# Top.net
KiCad netlist of a schematic drawn in Altium Designer
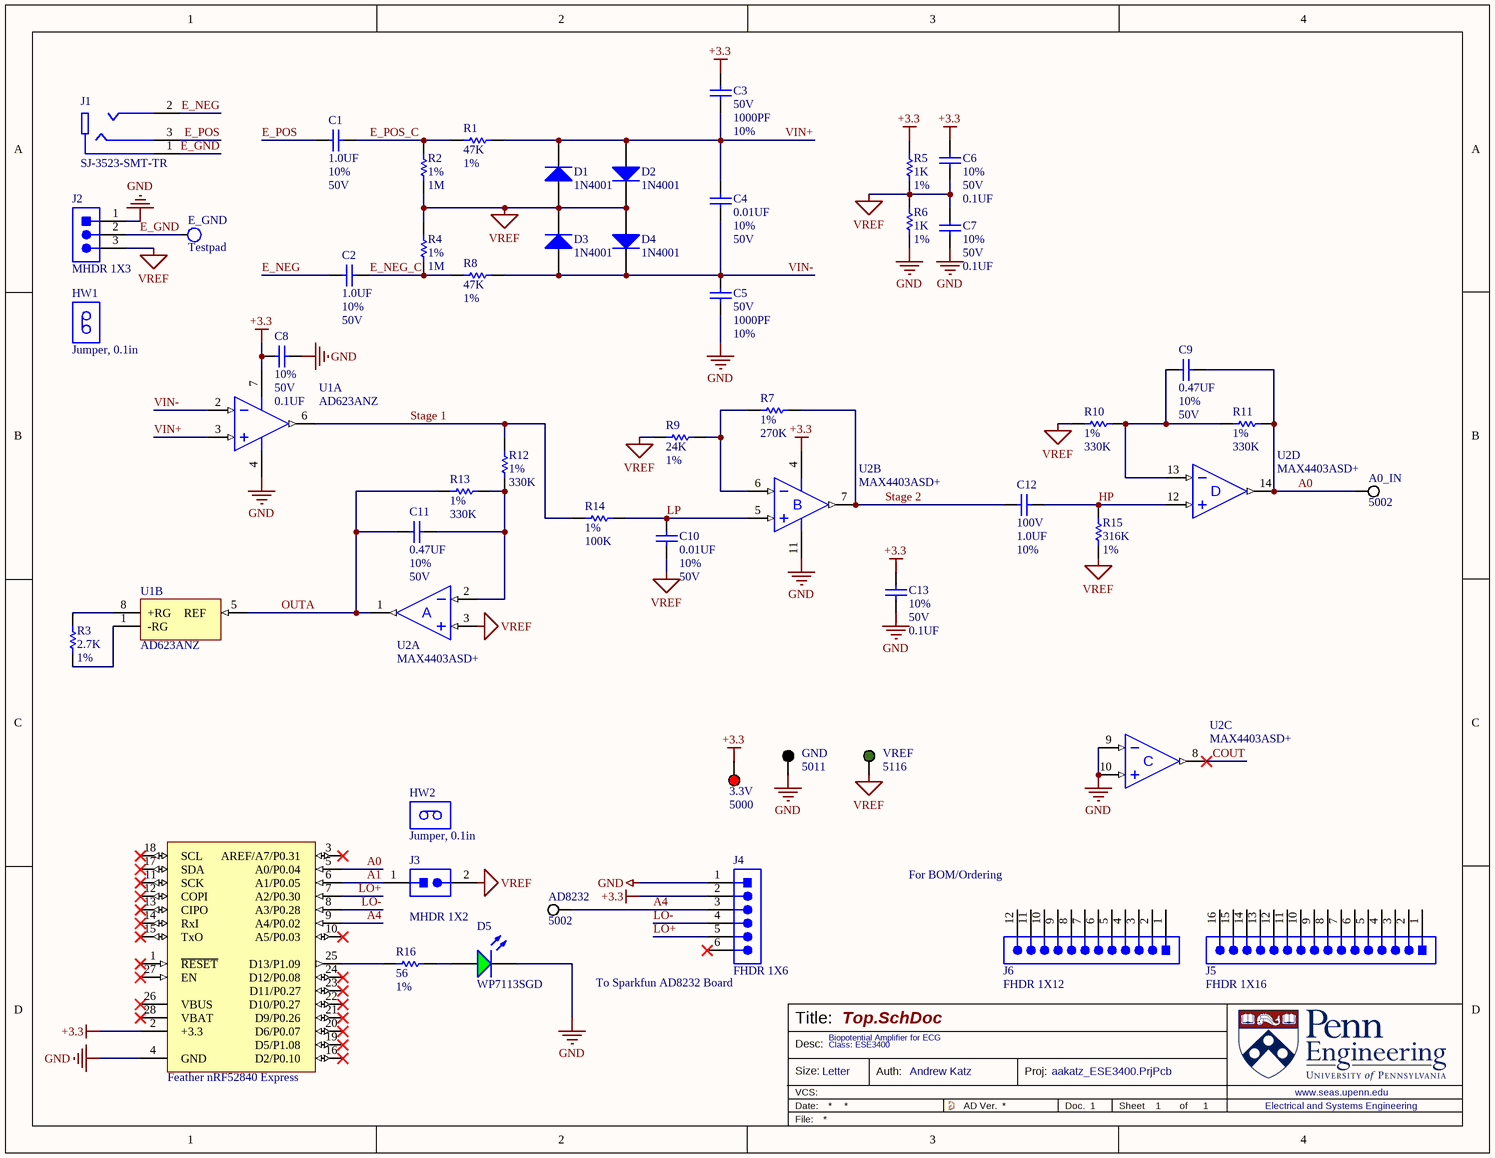
[diagram p0: Top.SchDoc]

(export (version "E")
  (design (tool "Eeschema 10.0.6"))
  (components
    (comp (ref "3.3V")
      (value "5000")
      (footprint "KSTN-5000")
      (description "Test Point, Red, 1-Pin THD, RoHS, Bulk")
      (fields (field (name "MANUFACTURER") "KeystoneElectronics"))
      (libsource (lib "University of Pennsylvania (ESE Labs)") (part "5000"))
    )
    (comp (ref "A0_IN")
      (value "5002")
      (footprint "KSTN-5002")
      (description "Test Point, White, 1-Pin THD, RoHS, Bulk")
      (fields (field (name "MANUFACTURER") "KeystoneElectronics"))
      (libsource (lib "University of Pennsylvania (ESE Labs)") (part "5002"))
    )
    (comp (ref "A1")
      (value "Feather nRF52840 Express")
      (footprint "4062-Stacking Headers")
      (description "Adafruit Feather nRF52840 Express (4062)")
      (libsource (lib "University of Pennsylvania (ESE Labs)") (part "4062-Symbol-1"))
    )
    (comp (ref "AD8232")
      (value "5002")
      (footprint "KSTN-5002")
      (description "Test Point, White, 1-Pin THD, RoHS, Bulk")
      (fields (field (name "MANUFACTURER") "KeystoneElectronics"))
      (libsource (lib "University of Pennsylvania (ESE Labs)") (part "5002"))
    )
    (comp (ref "C1")
      (value "1.0UF")
      (footprint "1206_CAP")
      (description "Capacitor Surface Mount 1206 Footprint 1.0UF 50V 10% Tolerance Ceramic X7R")
      (fields
        (field (name "TOLERANCE") "10%")
        (field (name "VOLTAGE") "50V")
        (field (name "MANUFACTURER") "Various")
        (field (name "Comment") "CAP 1206 1.0UF 50V 10% X7R")
      )
      (libsource (lib "University of Pennsylvania (ESE Labs)") (part "cap"))
    )
    (comp (ref "C2")
      (value "1.0UF")
      (footprint "1206_CAP")
      (description "Capacitor Surface Mount 1206 Footprint 1.0UF 50V 10% Tolerance Ceramic X7R")
      (fields
        (field (name "TOLERANCE") "10%")
        (field (name "VOLTAGE") "50V")
        (field (name "MANUFACTURER") "Various")
        (field (name "Comment") "CAP 1206 1.0UF 50V 10% X7R")
      )
      (libsource (lib "University of Pennsylvania (ESE Labs)") (part "cap"))
    )
    (comp (ref "C3")
      (value "1000PF")
      (footprint "1206_CAP")
      (description "Capacitor Surface Mount 1206 Footprint 1000PF 50V 10% Tolerance Ceramic X7R")
      (fields
        (field (name "VOLTAGE") "50V")
        (field (name "TOLERANCE") "10%")
        (field (name "MANUFACTURER") "Various")
        (field (name "Comment") "CAP 1206 1000PF 50V 10% X7R")
      )
      (libsource (lib "University of Pennsylvania (ESE Labs)") (part "cap"))
    )
    (comp (ref "C4")
      (value "0.01UF")
      (footprint "1206_CAP")
      (description "Capacitor Surface Mount 1206 Footprint 0.01UF 50V 10% Tolerance Ceramic X7R")
      (fields
        (field (name "MANUFACTURER") "Various")
        (field (name "TOLERANCE") "10%")
        (field (name "VOLTAGE") "50V")
        (field (name "Comment") "CAP 1206 0.01UF 50V 10% X7R")
      )
      (libsource (lib "University of Pennsylvania (ESE Labs)") (part "cap"))
    )
    (comp (ref "C5")
      (value "1000PF")
      (footprint "1206_CAP")
      (description "Capacitor Surface Mount 1206 Footprint 1000PF 50V 10% Tolerance Ceramic X7R")
      (fields
        (field (name "VOLTAGE") "50V")
        (field (name "TOLERANCE") "10%")
        (field (name "MANUFACTURER") "Various")
        (field (name "Comment") "CAP 1206 1000PF 50V 10% X7R")
      )
      (libsource (lib "University of Pennsylvania (ESE Labs)") (part "cap"))
    )
    (comp (ref "C6")
      (value "0.1UF")
      (footprint "1206_cap_35H")
      (description "Capacitor Surface Mount 1206 Footprint 0.1UF 50V 10% Tolerance Ceramic X7R")
      (fields
        (field (name "TOLERANCE") "10%")
        (field (name "MANUFACTURER") "KEMET")
        (field (name "VOLTAGE") "50V")
        (field (name "Comment") "CAP 1206 0.1UF 50V 10% X7R")
      )
      (libsource (lib "University of Pennsylvania (ESE Labs)") (part "cap"))
    )
    (comp (ref "C7")
      (value "0.1UF")
      (footprint "1206_cap_35H")
      (description "Capacitor Surface Mount 1206 Footprint 0.1UF 50V 10% Tolerance Ceramic X7R")
      (fields
        (field (name "TOLERANCE") "10%")
        (field (name "MANUFACTURER") "KEMET")
        (field (name "VOLTAGE") "50V")
        (field (name "Comment") "CAP 1206 0.1UF 50V 10% X7R")
      )
      (libsource (lib "University of Pennsylvania (ESE Labs)") (part "cap"))
    )
    (comp (ref "C8")
      (value "0.1UF")
      (footprint "1206_cap_35H")
      (description "Capacitor Surface Mount 1206 Footprint 0.1UF 50V 10% Tolerance Ceramic X7R")
      (fields
        (field (name "TOLERANCE") "10%")
        (field (name "MANUFACTURER") "KEMET")
        (field (name "VOLTAGE") "50V")
        (field (name "Comment") "CAP 1206 0.1UF 50V 10% X7R")
      )
      (libsource (lib "University of Pennsylvania (ESE Labs)") (part "cap"))
    )
    (comp (ref "C9")
      (value "0.47UF")
      (footprint "1206_CAP")
      (description "Capacitor Surface Mount 1206 Footprint 0.47UF 50V 10% Tolerance Ceramic X7R")
      (fields
        (field (name "MANUFACTURER") "Various")
        (field (name "TOLERANCE") "10%")
        (field (name "VOLTAGE") "50V")
        (field (name "Comment") "CAP 1206 0.47UF 50V 10% X7R")
      )
      (libsource (lib "University of Pennsylvania (ESE Labs)") (part "cap"))
    )
    (comp (ref "C10")
      (value "0.01UF")
      (footprint "1206_CAP")
      (description "Capacitor Surface Mount 1206 Footprint 0.01UF 50V 10% Tolerance Ceramic X7R")
      (fields
        (field (name "MANUFACTURER") "Various")
        (field (name "TOLERANCE") "10%")
        (field (name "VOLTAGE") "50V")
        (field (name "Comment") "CAP 1206 0.01UF 50V 10% X7R")
      )
      (libsource (lib "University of Pennsylvania (ESE Labs)") (part "cap"))
    )
    (comp (ref "C11")
      (value "0.47UF")
      (footprint "1206_CAP")
      (description "Capacitor Surface Mount 1206 Footprint 0.47UF 50V 10% Tolerance Ceramic X7R")
      (fields
        (field (name "MANUFACTURER") "Various")
        (field (name "TOLERANCE") "10%")
        (field (name "VOLTAGE") "50V")
        (field (name "Comment") "CAP 1206 0.47UF 50V 10% X7R")
      )
      (libsource (lib "University of Pennsylvania (ESE Labs)") (part "cap"))
    )
    (comp (ref "C12")
      (value "1.0UF")
      (footprint "1206_CAP")
      (description "Capacitor Surface Mount 1206 Footprint 1.0UF 100V 10% Tolerance Ceramic X7R")
      (fields
        (field (name "VOLTAGE") "100V")
        (field (name "MANUFACTURER") "Various")
        (field (name "TOLERANCE") "10%")
        (field (name "Comment") "CAP 1206 1.0UF 100V 10% X7R")
      )
      (libsource (lib "University of Pennsylvania (ESE Labs)") (part "cap"))
    )
    (comp (ref "C13")
      (value "0.1UF")
      (footprint "1206_cap_35H")
      (description "Capacitor Surface Mount 1206 Footprint 0.1UF 50V 10% Tolerance Ceramic X7R")
      (fields
        (field (name "TOLERANCE") "10%")
        (field (name "MANUFACTURER") "KEMET")
        (field (name "VOLTAGE") "50V")
        (field (name "Comment") "CAP 1206 0.1UF 50V 10% X7R")
      )
      (libsource (lib "University of Pennsylvania (ESE Labs)") (part "cap"))
    )
    (comp (ref "D1")
      (value "1N4001")
      (footprint "DO-41 0.4in Spacing")
      (description "Rectifier Diode, 1 Phase, 1 Element, 1A, 50V V(RRM), Silicon, DO-41")
      (libsource (lib "University of Pennsylvania (ESE Labs)") (part "Diode"))
    )
    (comp (ref "D2")
      (value "1N4001")
      (footprint "DO-41 0.4in Spacing")
      (description "Rectifier Diode, 1 Phase, 1 Element, 1A, 50V V(RRM), Silicon, DO-41")
      (libsource (lib "University of Pennsylvania (ESE Labs)") (part "Diode"))
    )
    (comp (ref "D3")
      (value "1N4001")
      (footprint "DO-41 0.4in Spacing")
      (description "Rectifier Diode, 1 Phase, 1 Element, 1A, 50V V(RRM), Silicon, DO-41")
      (libsource (lib "University of Pennsylvania (ESE Labs)") (part "Diode"))
    )
    (comp (ref "D4")
      (value "1N4001")
      (footprint "DO-41 0.4in Spacing")
      (description "Rectifier Diode, 1 Phase, 1 Element, 1A, 50V V(RRM), Silicon, DO-41")
      (libsource (lib "University of Pennsylvania (ESE Labs)") (part "Diode"))
    )
    (comp (ref "D5")
      (value "WP7113SGD")
      (footprint "T-1 3/4 LED")
      (description "Single Color LED, Super Bright Green, Diffused Green, T-1 3/4, 5mm")
      (libsource (lib "University of Pennsylvania (ESE Labs)") (part "LED-GREEN-AK-2"))
    )
    (comp (ref "E_GND")
      (value "Testpad")
      (footprint "Test PTH 15-30")
      (description "Test Pad/Point")
      (libsource (lib "University of Pennsylvania (ESE Labs)") (part "30mm Test Pad"))
    )
    (comp (ref "GND")
      (value "5011")
      (footprint "KSTN-5011_V")
      (description "Large THT Test Point, Black")
      (libsource (lib "University of Pennsylvania (ESE Labs)") (part "TESTPOINT_BLACK"))
    )
    (comp (ref "HW1")
      (value "Jumper, 0.1in")
      (description "2 (1 x 2) Position Shunt Connector, No Grip 0.100\" (2.54mm) Gold")
      (libsource (lib "University of Pennsylvania (ESE Labs)") (part "Shunt Jumper Symbol"))
    )
    (comp (ref "HW2")
      (value "Jumper, 0.1in")
      (description "2 (1 x 2) Position Shunt Connector, No Grip 0.100\" (2.54mm) Gold")
      (libsource (lib "University of Pennsylvania (ESE Labs)") (part "Shunt Jumper Symbol"))
    )
    (comp (ref "J1")
      (value "SJ-3523-SMT-TR")
      (footprint "SJ-3524-SMT-TR-Footprint-1")
      (description "3 Pole(s), Female, Surface Mount Terminal, Locking, Jack")
      (libsource (lib "University of Pennsylvania (ESE Labs)") (part "SJ-3524-SMT-TR-Symbol-1"))
    )
    (comp (ref "J2")
      (value "MHDR 1X3")
      (footprint "PH1-03-UA")
      (description "Header, 3-Pin, 0.1in Pitch, Male")
      (libsource (lib "University of Pennsylvania (ESE Labs)") (part "Header 1X3"))
    )
    (comp (ref "J3")
      (value "MHDR 1X2")
      (footprint "PH1-02-UA")
      (description "Header, 2-Pin, 0.1in Pitch, Male")
      (libsource (lib "University of Pennsylvania (ESE Labs)") (part "Header 1X2"))
    )
    (comp (ref "J4")
      (value "FHDR 1X6")
      (footprint "FHDR 1X6-Footprint-1")
      (libsource (lib "University of Pennsylvania (ESE Labs)") (part "Header 1X6"))
    )
    (comp (ref "J5")
      (value "FHDR 1X16")
      (footprint "FHDR 1X16-Footprint-1")
      (description "Header, 16-Pin, 0.1in Pitch, Female")
      (libsource (lib "University of Pennsylvania (ESE Labs)") (part "Header 1X16"))
    )
    (comp (ref "J6")
      (value "FHDR 1X12")
      (footprint "M20-7821246-Footprint-1")
      (libsource (lib "University of Pennsylvania (ESE Labs)") (part "Header 1X12"))
    )
    (comp (ref "R1")
      (value "47K")
      (footprint "0805_RES")
      (description "Resistor Surface Mount, 47K Ohms, 0805 Footprint, 1% Tolerance 0.125W")
      (fields
        (field (name "MANUFACTURER") "Various")
        (field (name "TOLERANCE") "1%")
        (field (name "Comment") "RES 0805 47K 1%")
      )
      (libsource (lib "University of Pennsylvania (ESE Labs)") (part "res"))
    )
    (comp (ref "R2")
      (value "1M")
      (footprint "0805_RES")
      (description "Resistor Surface Mount, 1M Ohms, 0805 Footprint, 1% Tolerance 0.125W")
      (fields
        (field (name "MANUFACTURER") "Various")
        (field (name "TOLERANCE") "1%")
        (field (name "Comment") "RES 0805 1M 1%")
      )
      (libsource (lib "University of Pennsylvania (ESE Labs)") (part "res"))
    )
    (comp (ref "R3")
      (value "2.7K")
      (footprint "0805_RES")
      (description "Resistor Surface Mount, 2.7K Ohms, 0805 Footprint, 1% Tolerance 0.125W")
      (fields
        (field (name "MANUFACTURER") "Various")
        (field (name "TOLERANCE") "1%")
        (field (name "Comment") "RES 0805 2.7K 1%")
      )
      (libsource (lib "University of Pennsylvania (ESE Labs)") (part "res"))
    )
    (comp (ref "R4")
      (value "1M")
      (footprint "0805_RES")
      (description "Resistor Surface Mount, 1M Ohms, 0805 Footprint, 1% Tolerance 0.125W")
      (fields
        (field (name "MANUFACTURER") "Various")
        (field (name "TOLERANCE") "1%")
        (field (name "Comment") "RES 0805 1M 1%")
      )
      (libsource (lib "University of Pennsylvania (ESE Labs)") (part "res"))
    )
    (comp (ref "R5")
      (value "1K")
      (footprint "0805_RES")
      (description "Resistor Surface Mount, 1K Ohms, 0805 Footprint, 1% Tolerance 0.125W")
      (fields
        (field (name "MANUFACTURER") "Various")
        (field (name "TOLERANCE") "1%")
        (field (name "Comment") "RES 0805 1K 1%")
      )
      (libsource (lib "University of Pennsylvania (ESE Labs)") (part "res"))
    )
    (comp (ref "R6")
      (value "1K")
      (footprint "0805_RES")
      (description "Resistor Surface Mount, 1K Ohms, 0805 Footprint, 1% Tolerance 0.125W")
      (fields
        (field (name "MANUFACTURER") "Various")
        (field (name "TOLERANCE") "1%")
        (field (name "Comment") "RES 0805 1K 1%")
      )
      (libsource (lib "University of Pennsylvania (ESE Labs)") (part "res"))
    )
    (comp (ref "R7")
      (value "270K")
      (footprint "0805_RES")
      (description "Resistor Surface Mount, 270K Ohms, 0805 Footprint, 1% Tolerance 0.125W")
      (fields
        (field (name "TOLERANCE") "1%")
        (field (name "MANUFACTURER") "Various")
        (field (name "Comment") "RES 0805 270K 1%")
      )
      (libsource (lib "University of Pennsylvania (ESE Labs)") (part "res"))
    )
    (comp (ref "R8")
      (value "47K")
      (footprint "0805_RES")
      (description "Resistor Surface Mount, 47K Ohms, 0805 Footprint, 1% Tolerance 0.125W")
      (fields
        (field (name "MANUFACTURER") "Various")
        (field (name "TOLERANCE") "1%")
        (field (name "Comment") "RES 0805 47K 1%")
      )
      (libsource (lib "University of Pennsylvania (ESE Labs)") (part "res"))
    )
    (comp (ref "R9")
      (value "24K")
      (footprint "0805_RES")
      (description "Resistor Surface Mount, 24K Ohms, 0805 Footprint, 1% Tolerance 0.125W")
      (fields
        (field (name "MANUFACTURER") "Various")
        (field (name "TOLERANCE") "1%")
        (field (name "Comment") "RES 0805 24K 1%")
      )
      (libsource (lib "University of Pennsylvania (ESE Labs)") (part "res"))
    )
    (comp (ref "R10")
      (value "330K")
      (footprint "0805_RES")
      (description "Resistor Surface Mount, 330K Ohms, 0805 Footprint, 1% Tolerance 0.125W")
      (fields
        (field (name "TOLERANCE") "1%")
        (field (name "MANUFACTURER") "Various")
        (field (name "Comment") "RES 0805 330K 1%")
      )
      (libsource (lib "University of Pennsylvania (ESE Labs)") (part "res"))
    )
    (comp (ref "R11")
      (value "330K")
      (footprint "0805_RES")
      (description "Resistor Surface Mount, 330K Ohms, 0805 Footprint, 1% Tolerance 0.125W")
      (fields
        (field (name "TOLERANCE") "1%")
        (field (name "MANUFACTURER") "Various")
        (field (name "Comment") "RES 0805 330K 1%")
      )
      (libsource (lib "University of Pennsylvania (ESE Labs)") (part "res"))
    )
    (comp (ref "R12")
      (value "330K")
      (footprint "0805_RES")
      (description "Resistor Surface Mount, 330K Ohms, 0805 Footprint, 1% Tolerance 0.125W")
      (fields
        (field (name "TOLERANCE") "1%")
        (field (name "MANUFACTURER") "Various")
        (field (name "Comment") "RES 0805 330K 1%")
      )
      (libsource (lib "University of Pennsylvania (ESE Labs)") (part "res"))
    )
    (comp (ref "R13")
      (value "330K")
      (footprint "0805_RES")
      (description "Resistor Surface Mount, 330K Ohms, 0805 Footprint, 1% Tolerance 0.125W")
      (fields
        (field (name "TOLERANCE") "1%")
        (field (name "MANUFACTURER") "Various")
        (field (name "Comment") "RES 0805 330K 1%")
      )
      (libsource (lib "University of Pennsylvania (ESE Labs)") (part "res"))
    )
    (comp (ref "R14")
      (value "100K")
      (footprint "0805_RES")
      (description "Resistor Surface Mount, 100K Ohms, 0805 Footprint, 1% Tolerance 0.125W")
      (fields
        (field (name "TOLERANCE") "1%")
        (field (name "MANUFACTURER") "Various")
        (field (name "Comment") "RES 0805 100K 1%")
      )
      (libsource (lib "University of Pennsylvania (ESE Labs)") (part "res"))
    )
    (comp (ref "R15")
      (value "316K")
      (footprint "0805_RES")
      (description "Resistor Surface Mount, 316K Ohms, 0805 Footprint, 1% Tolerance 0.125W")
      (fields
        (field (name "MANUFACTURER") "Various")
        (field (name "TOLERANCE") "1%")
        (field (name "Comment") "RES 0805 316K 1%")
      )
      (libsource (lib "University of Pennsylvania (ESE Labs)") (part "res"))
    )
    (comp (ref "R16")
      (value "56")
      (footprint "0805_RES")
      (description "Resistor Surface Mount, 56 Ohms, 0805 Footprint, 1% Tolerance 0.125W")
      (fields
        (field (name "MANUFACTURER") "Various")
        (field (name "TOLERANCE") "1%")
        (field (name "Comment") "RES 0805 56 1%")
      )
      (libsource (lib "University of Pennsylvania (ESE Labs)") (part "res"))
    )
    (comp (ref "U1")
      (value "AD623ANZ")
      (footprint "DIP8-SOCKETED")
      (description "Instrumentation Amplifier, 1 Func, 350uV Offset-Max, 0.8MHz Band Width, PDIP8")
      (libsource (lib "University of Pennsylvania (ESE Labs)") (part "AD623-Sym"))
    )
    (comp (ref "U2")
      (value "MAX4403ASD+")
      (footprint "AD8694ARZ-Footprint-1")
      (description "Operational Amplifier, 4 Func, 8000uV Offset-Max, CMOS, PDSO14")
      (libsource (lib "University of Pennsylvania (ESE Labs)") (part "AMP-OPA-LM124-14"))
    )
    (comp (ref "VREF")
      (value "5116")
      (footprint "KSTN-5116")
      (description "Test Point, Green, 1-Pin THD, RoHS, Bulk")
      (fields (field (name "MANUFACTURER") "KeystoneElectronics"))
      (libsource (lib "University of Pennsylvania (ESE Labs)") (part "5116"))
    )
  )
  (nets
    (net (code "1") (name "+3.3") (class "Default")
      (node (ref "3.3V") (pin "1") (pintype "passive"))
      (node (ref "A1") (pin "2") (pinfunction "+3.3_2") (pintype "power_in"))
      (node (ref "C13") (pin "1") (pinfunction "1_1") (pintype "passive"))
      (node (ref "C3") (pin "2") (pinfunction "2_2") (pintype "passive"))
      (node (ref "C6") (pin "1") (pinfunction "1_1") (pintype "passive"))
      (node (ref "C8") (pin "1") (pinfunction "1_1") (pintype "passive"))
      (node (ref "J4") (pin "2") (pinfunction "2_2") (pintype "passive"))
      (node (ref "R5") (pin "2") (pinfunction "2_2") (pintype "passive"))
      (node (ref "U1") (pin "7") (pinfunction "V+_7") (pintype "power_in"))
      (node (ref "U2") (pin "4") (pinfunction "V+_4") (pintype "power_in"))
    )
    (net (code "2") (name "/A0") (class "Default")
      (node (ref "A0_IN") (pin "1") (pintype "passive"))
      (node (ref "A1") (pin "5") (pinfunction "A0/P0.04_5") (pintype "input"))
      (node (ref "C9") (pin "2") (pinfunction "2_2") (pintype "passive"))
      (node (ref "R11") (pin "2") (pinfunction "2_2") (pintype "passive"))
      (node (ref "U2") (pin "14") (pinfunction "OUT4_14") (pintype "output"))
    )
    (net (code "3") (name "/A1") (class "Default")
      (node (ref "A1") (pin "6") (pinfunction "A1/P0.05_6") (pintype "input"))
      (node (ref "J3") (pin "1") (pinfunction "1_1") (pintype "passive"))
    )
    (net (code "4") (name "/A4") (class "Default")
      (node (ref "A1") (pin "9") (pinfunction "A4/P0.02_9") (pintype "input"))
      (node (ref "AD8232") (pin "1") (pintype "passive"))
      (node (ref "J4") (pin "3") (pinfunction "3_3") (pintype "passive"))
    )
    (net (code "5") (name "/COUT") (class "Default")
      (node (ref "U2") (pin "8") (pinfunction "OUT3_8") (pintype "output+no_connect"))
    )
    (net (code "6") (name "/E_GND") (class "Default")
      (node (ref "E_GND") (pin "1") (pinfunction "1_1") (pintype "passive"))
      (node (ref "J1") (pin "1") (pinfunction "Sleeve_1") (pintype "passive"))
      (node (ref "J2") (pin "2") (pinfunction "2_2") (pintype "passive"))
    )
    (net (code "7") (name "/E_NEG") (class "Default")
      (node (ref "C2") (pin "1") (pinfunction "1_1") (pintype "passive"))
      (node (ref "J1") (pin "2") (pinfunction "Tip_2") (pintype "passive"))
    )
    (net (code "8") (name "/E_NEG_C") (class "Default")
      (node (ref "C2") (pin "2") (pinfunction "2_2") (pintype "passive"))
      (node (ref "R4") (pin "1") (pinfunction "1_1") (pintype "passive"))
      (node (ref "R8") (pin "1") (pinfunction "1_1") (pintype "passive"))
    )
    (net (code "9") (name "/E_POS") (class "Default")
      (node (ref "C1") (pin "1") (pinfunction "1_1") (pintype "passive"))
      (node (ref "J1") (pin "3") (pinfunction "Ring_3") (pintype "passive"))
    )
    (net (code "10") (name "/E_POS_C") (class "Default")
      (node (ref "C1") (pin "2") (pinfunction "2_2") (pintype "passive"))
      (node (ref "R1") (pin "1") (pinfunction "1_1") (pintype "passive"))
      (node (ref "R2") (pin "2") (pinfunction "2_2") (pintype "passive"))
    )
    (net (code "11") (name "/HP") (class "Default")
      (node (ref "C12") (pin "2") (pinfunction "2_2") (pintype "passive"))
      (node (ref "R15") (pin "2") (pinfunction "2_2") (pintype "passive"))
      (node (ref "U2") (pin "12") (pinfunction "IN4+_12") (pintype "input"))
    )
    (net (code "12") (name "/LO+") (class "Default")
      (node (ref "A1") (pin "7") (pinfunction "A2/P0.30_7") (pintype "input"))
      (node (ref "J4") (pin "5") (pinfunction "5_5") (pintype "passive"))
    )
    (net (code "13") (name "/LO-") (class "Default")
      (node (ref "A1") (pin "8") (pinfunction "A3/P0.28_8") (pintype "input"))
      (node (ref "J4") (pin "4") (pinfunction "4_4") (pintype "passive"))
    )
    (net (code "14") (name "/LP") (class "Default")
      (node (ref "C10") (pin "1") (pinfunction "1_1") (pintype "passive"))
      (node (ref "R14") (pin "1") (pinfunction "1_1") (pintype "passive"))
      (node (ref "U2") (pin "5") (pinfunction "IN2+_5") (pintype "input"))
    )
    (net (code "15") (name "/OUTA") (class "Default")
      (node (ref "C11") (pin "1") (pinfunction "1_1") (pintype "passive"))
      (node (ref "R13") (pin "1") (pinfunction "1_1") (pintype "passive"))
      (node (ref "U1") (pin "5") (pinfunction "REF_5") (pintype "input"))
      (node (ref "U2") (pin "1") (pinfunction "OUT1_1") (pintype "output"))
    )
    (net (code "16") (name "/Stage 1") (class "Default")
      (node (ref "R12") (pin "2") (pinfunction "2_2") (pintype "passive"))
      (node (ref "R14") (pin "2") (pinfunction "2_2") (pintype "passive"))
      (node (ref "U1") (pin "6") (pinfunction "OUT_6") (pintype "output"))
    )
    (net (code "17") (name "/Stage 2") (class "Default")
      (node (ref "C12") (pin "1") (pinfunction "1_1") (pintype "passive"))
      (node (ref "R7") (pin "2") (pinfunction "2_2") (pintype "passive"))
      (node (ref "U2") (pin "7") (pinfunction "OUT2_7") (pintype "output"))
    )
    (net (code "18") (name "/VIN+") (class "Default")
      (node (ref "C3") (pin "1") (pinfunction "1_1") (pintype "passive"))
      (node (ref "C4") (pin "2") (pinfunction "2_2") (pintype "passive"))
      (node (ref "D1") (pin "K") (pinfunction "K_K") (pintype "passive"))
      (node (ref "D2") (pin "A") (pinfunction "A_A") (pintype "passive"))
      (node (ref "R1") (pin "2") (pinfunction "2_2") (pintype "passive"))
      (node (ref "U1") (pin "3") (pinfunction "IN1+_3") (pintype "input"))
    )
    (net (code "19") (name "/VIN-") (class "Default")
      (node (ref "C4") (pin "1") (pinfunction "1_1") (pintype "passive"))
      (node (ref "C5") (pin "2") (pinfunction "2_2") (pintype "passive"))
      (node (ref "D3") (pin "A") (pinfunction "A_A") (pintype "passive"))
      (node (ref "D4") (pin "K") (pinfunction "K_K") (pintype "passive"))
      (node (ref "R8") (pin "2") (pinfunction "2_2") (pintype "passive"))
      (node (ref "U1") (pin "2") (pinfunction "IN1-_2") (pintype "input"))
    )
    (net (code "20") (name "GND") (class "Default")
      (node (ref "A1") (pin "4") (pinfunction "GND_4") (pintype "power_in"))
      (node (ref "C13") (pin "2") (pinfunction "2_2") (pintype "passive"))
      (node (ref "C5") (pin "1") (pinfunction "1_1") (pintype "passive"))
      (node (ref "C7") (pin "2") (pinfunction "2_2") (pintype "passive"))
      (node (ref "C8") (pin "2") (pinfunction "2_2") (pintype "passive"))
      (node (ref "D5") (pin "K") (pinfunction "K_K") (pintype "passive"))
      (node (ref "GND") (pin "1") (pinfunction "1_1") (pintype "passive"))
      (node (ref "J2") (pin "1") (pinfunction "1_1") (pintype "passive"))
      (node (ref "J4") (pin "1") (pinfunction "1_1") (pintype "passive"))
      (node (ref "R6") (pin "1") (pinfunction "1_1") (pintype "passive"))
      (node (ref "U1") (pin "4") (pinfunction "V-_4") (pintype "power_in"))
      (node (ref "U2") (pin "10") (pinfunction "IN3+_10") (pintype "input"))
      (node (ref "U2") (pin "11") (pinfunction "GND_11") (pintype "power_in"))
      (node (ref "U2") (pin "9") (pinfunction "IN3-_9") (pintype "input"))
    )
    (net (code "21") (name "Net-(A1-D13{slash}P1.09)") (class "Default")
      (node (ref "A1") (pin "25") (pinfunction "D13/P1.09_25") (pintype "output"))
      (node (ref "R16") (pin "1") (pinfunction "1_1") (pintype "passive"))
    )
    (net (code "22") (name "Net-(D5-PadA)") (class "Default")
      (node (ref "D5") (pin "A") (pinfunction "A_A") (pintype "passive"))
      (node (ref "R16") (pin "2") (pinfunction "2_2") (pintype "passive"))
    )
    (net (code "23") (name "Net-(U1B-+RG)") (class "Default")
      (node (ref "R3") (pin "2") (pinfunction "2_2") (pintype "passive"))
      (node (ref "U1") (pin "8") (pinfunction "+RG_8") (pintype "passive"))
    )
    (net (code "24") (name "Net-(U1B--RG)") (class "Default")
      (node (ref "R3") (pin "1") (pinfunction "1_1") (pintype "passive"))
      (node (ref "U1") (pin "1") (pinfunction "-RG_1") (pintype "passive"))
    )
    (net (code "25") (name "Net-(U2A-IN1-)") (class "Default")
      (node (ref "C11") (pin "2") (pinfunction "2_2") (pintype "passive"))
      (node (ref "R12") (pin "1") (pinfunction "1_1") (pintype "passive"))
      (node (ref "R13") (pin "2") (pinfunction "2_2") (pintype "passive"))
      (node (ref "U2") (pin "2") (pinfunction "IN1-_2") (pintype "input"))
    )
    (net (code "26") (name "Net-(U2B-IN2-)") (class "Default")
      (node (ref "R7") (pin "1") (pinfunction "1_1") (pintype "passive"))
      (node (ref "R9") (pin "2") (pinfunction "2_2") (pintype "passive"))
      (node (ref "U2") (pin "6") (pinfunction "IN2-_6") (pintype "input"))
    )
    (net (code "27") (name "Net-(U2D-IN4-)") (class "Default")
      (node (ref "C9") (pin "1") (pinfunction "1_1") (pintype "passive"))
      (node (ref "R10") (pin "2") (pinfunction "2_2") (pintype "passive"))
      (node (ref "R11") (pin "1") (pinfunction "1_1") (pintype "passive"))
      (node (ref "U2") (pin "13") (pinfunction "IN4-_13") (pintype "input"))
    )
    (net (code "28") (name "VREF") (class "Default")
      (node (ref "C10") (pin "2") (pinfunction "2_2") (pintype "passive"))
      (node (ref "C6") (pin "2") (pinfunction "2_2") (pintype "passive"))
      (node (ref "C7") (pin "1") (pinfunction "1_1") (pintype "passive"))
      (node (ref "D1") (pin "A") (pinfunction "A_A") (pintype "passive"))
      (node (ref "D2") (pin "K") (pinfunction "K_K") (pintype "passive"))
      (node (ref "D3") (pin "K") (pinfunction "K_K") (pintype "passive"))
      (node (ref "D4") (pin "A") (pinfunction "A_A") (pintype "passive"))
      (node (ref "J2") (pin "3") (pinfunction "3_3") (pintype "passive"))
      (node (ref "J3") (pin "2") (pinfunction "2_2") (pintype "passive"))
      (node (ref "R10") (pin "1") (pinfunction "1_1") (pintype "passive"))
      (node (ref "R15") (pin "1") (pinfunction "1_1") (pintype "passive"))
      (node (ref "R2") (pin "1") (pinfunction "1_1") (pintype "passive"))
      (node (ref "R4") (pin "2") (pinfunction "2_2") (pintype "passive"))
      (node (ref "R5") (pin "1") (pinfunction "1_1") (pintype "passive"))
      (node (ref "R6") (pin "2") (pinfunction "2_2") (pintype "passive"))
      (node (ref "R9") (pin "1") (pinfunction "1_1") (pintype "passive"))
      (node (ref "U2") (pin "3") (pinfunction "IN1+_3") (pintype "input"))
      (node (ref "VREF") (pin "1") (pintype "passive"))
    )
    (net (code "29") (name "unconnected-(A1-A5{slash}P0.03-Pad10)") (class "Default")
      (node (ref "A1") (pin "10") (pinfunction "A5/P0.03_10") (pintype "bidirectional+no_connect"))
    )
    (net (code "30") (name "unconnected-(A1-AREF{slash}A7{slash}P0.31-Pad3)") (class "Default")
      (node (ref "A1") (pin "3") (pinfunction "AREF/A7/P0.31_3") (pintype "bidirectional+no_connect"))
    )
    (net (code "31") (name "unconnected-(A1-CIPO-Pad13)") (class "Default")
      (node (ref "A1") (pin "13") (pinfunction "CIPO_13") (pintype "bidirectional+no_connect"))
    )
    (net (code "32") (name "unconnected-(A1-COPI-Pad12)") (class "Default")
      (node (ref "A1") (pin "12") (pinfunction "COPI_12") (pintype "bidirectional+no_connect"))
    )
    (net (code "33") (name "unconnected-(A1-D2{slash}P0.10-Pad16)") (class "Default")
      (node (ref "A1") (pin "16") (pinfunction "D2/P0.10_16") (pintype "bidirectional+no_connect"))
    )
    (net (code "34") (name "unconnected-(A1-D5{slash}P1.08-Pad19)") (class "Default")
      (node (ref "A1") (pin "19") (pinfunction "D5/P1.08_19") (pintype "bidirectional+no_connect"))
    )
    (net (code "35") (name "unconnected-(A1-D6{slash}P0.07-Pad20)") (class "Default")
      (node (ref "A1") (pin "20") (pinfunction "D6/P0.07_20") (pintype "bidirectional+no_connect"))
    )
    (net (code "36") (name "unconnected-(A1-D9{slash}P0.26-Pad21)") (class "Default")
      (node (ref "A1") (pin "21") (pinfunction "D9/P0.26_21") (pintype "bidirectional+no_connect"))
    )
    (net (code "37") (name "unconnected-(A1-D10{slash}P0.27-Pad22)") (class "Default")
      (node (ref "A1") (pin "22") (pinfunction "D10/P0.27_22") (pintype "bidirectional+no_connect"))
    )
    (net (code "38") (name "unconnected-(A1-D11{slash}P0.27-Pad23)") (class "Default")
      (node (ref "A1") (pin "23") (pinfunction "D11/P0.27_23") (pintype "bidirectional+no_connect"))
    )
    (net (code "39") (name "unconnected-(A1-D12{slash}P0.08-Pad24)") (class "Default")
      (node (ref "A1") (pin "24") (pinfunction "D12/P0.08_24") (pintype "bidirectional+no_connect"))
    )
    (net (code "40") (name "unconnected-(A1-EN-Pad27)") (class "Default")
      (node (ref "A1") (pin "27") (pinfunction "EN_27") (pintype "input+no_connect"))
    )
    (net (code "41") (name "unconnected-(A1-RESET-Pad1)") (class "Default")
      (node (ref "A1") (pin "1") (pinfunction "RESET_1") (pintype "input+no_connect"))
    )
    (net (code "42") (name "unconnected-(A1-RxI-Pad14)") (class "Default")
      (node (ref "A1") (pin "14") (pinfunction "RxI_14") (pintype "bidirectional+no_connect"))
    )
    (net (code "43") (name "unconnected-(A1-SCK-Pad11)") (class "Default")
      (node (ref "A1") (pin "11") (pinfunction "SCK_11") (pintype "bidirectional+no_connect"))
    )
    (net (code "44") (name "unconnected-(A1-SCL-Pad18)") (class "Default")
      (node (ref "A1") (pin "18") (pinfunction "SCL_18") (pintype "bidirectional+no_connect"))
    )
    (net (code "45") (name "unconnected-(A1-SDA-Pad17)") (class "Default")
      (node (ref "A1") (pin "17") (pinfunction "SDA_17") (pintype "bidirectional+no_connect"))
    )
    (net (code "46") (name "unconnected-(A1-TxO-Pad15)") (class "Default")
      (node (ref "A1") (pin "15") (pinfunction "TxO_15") (pintype "bidirectional+no_connect"))
    )
    (net (code "47") (name "unconnected-(A1-VBAT-Pad28)") (class "Default")
      (node (ref "A1") (pin "28") (pinfunction "VBAT_28") (pintype "power_in+no_connect"))
    )
    (net (code "48") (name "unconnected-(A1-VBUS-Pad26)") (class "Default")
      (node (ref "A1") (pin "26") (pinfunction "VBUS_26") (pintype "power_in+no_connect"))
    )
    (net (code "49") (name "unconnected-(J4-Pad6)") (class "Default")
      (node (ref "J4") (pin "6") (pinfunction "6_6") (pintype "passive+no_connect"))
    )
    (net (code "50") (name "unconnected-(J5-Pad1)") (class "Default")
      (node (ref "J5") (pin "1") (pinfunction "1_1") (pintype "passive"))
    )
    (net (code "51") (name "unconnected-(J5-Pad2)") (class "Default")
      (node (ref "J5") (pin "2") (pinfunction "2_2") (pintype "passive"))
    )
    (net (code "52") (name "unconnected-(J5-Pad3)") (class "Default")
      (node (ref "J5") (pin "3") (pinfunction "3_3") (pintype "passive"))
    )
    (net (code "53") (name "unconnected-(J5-Pad4)") (class "Default")
      (node (ref "J5") (pin "4") (pinfunction "4_4") (pintype "passive"))
    )
    (net (code "54") (name "unconnected-(J5-Pad5)") (class "Default")
      (node (ref "J5") (pin "5") (pinfunction "5_5") (pintype "passive"))
    )
    (net (code "55") (name "unconnected-(J5-Pad6)") (class "Default")
      (node (ref "J5") (pin "6") (pinfunction "6_6") (pintype "passive"))
    )
    (net (code "56") (name "unconnected-(J5-Pad7)") (class "Default")
      (node (ref "J5") (pin "7") (pinfunction "7_7") (pintype "passive"))
    )
    (net (code "57") (name "unconnected-(J5-Pad8)") (class "Default")
      (node (ref "J5") (pin "8") (pinfunction "8_8") (pintype "passive"))
    )
    (net (code "58") (name "unconnected-(J5-Pad9)") (class "Default")
      (node (ref "J5") (pin "9") (pinfunction "9_9") (pintype "passive"))
    )
    (net (code "59") (name "unconnected-(J5-Pad10)") (class "Default")
      (node (ref "J5") (pin "10") (pinfunction "10_10") (pintype "passive"))
    )
    (net (code "60") (name "unconnected-(J5-Pad11)") (class "Default")
      (node (ref "J5") (pin "11") (pinfunction "11_11") (pintype "passive"))
    )
    (net (code "61") (name "unconnected-(J5-Pad12)") (class "Default")
      (node (ref "J5") (pin "12") (pinfunction "12_12") (pintype "passive"))
    )
    (net (code "62") (name "unconnected-(J5-Pad13)") (class "Default")
      (node (ref "J5") (pin "13") (pinfunction "13_13") (pintype "passive"))
    )
    (net (code "63") (name "unconnected-(J5-Pad14)") (class "Default")
      (node (ref "J5") (pin "14") (pinfunction "14_14") (pintype "passive"))
    )
    (net (code "64") (name "unconnected-(J5-Pad15)") (class "Default")
      (node (ref "J5") (pin "15") (pinfunction "15_15") (pintype "passive"))
    )
    (net (code "65") (name "unconnected-(J5-Pad16)") (class "Default")
      (node (ref "J5") (pin "16") (pinfunction "16_16") (pintype "passive"))
    )
    (net (code "66") (name "unconnected-(J6-Pad1)") (class "Default")
      (node (ref "J6") (pin "1") (pinfunction "1_1") (pintype "passive"))
    )
    (net (code "67") (name "unconnected-(J6-Pad2)") (class "Default")
      (node (ref "J6") (pin "2") (pinfunction "2_2") (pintype "passive"))
    )
    (net (code "68") (name "unconnected-(J6-Pad3)") (class "Default")
      (node (ref "J6") (pin "3") (pinfunction "3_3") (pintype "passive"))
    )
    (net (code "69") (name "unconnected-(J6-Pad4)") (class "Default")
      (node (ref "J6") (pin "4") (pinfunction "4_4") (pintype "passive"))
    )
    (net (code "70") (name "unconnected-(J6-Pad5)") (class "Default")
      (node (ref "J6") (pin "5") (pinfunction "5_5") (pintype "passive"))
    )
    (net (code "71") (name "unconnected-(J6-Pad6)") (class "Default")
      (node (ref "J6") (pin "6") (pinfunction "6_6") (pintype "passive"))
    )
    (net (code "72") (name "unconnected-(J6-Pad7)") (class "Default")
      (node (ref "J6") (pin "7") (pinfunction "7_7") (pintype "passive"))
    )
    (net (code "73") (name "unconnected-(J6-Pad8)") (class "Default")
      (node (ref "J6") (pin "8") (pinfunction "8_8") (pintype "passive"))
    )
    (net (code "74") (name "unconnected-(J6-Pad9)") (class "Default")
      (node (ref "J6") (pin "9") (pinfunction "9_9") (pintype "passive"))
    )
    (net (code "75") (name "unconnected-(J6-Pad10)") (class "Default")
      (node (ref "J6") (pin "10") (pinfunction "10_10") (pintype "passive"))
    )
    (net (code "76") (name "unconnected-(J6-Pad11)") (class "Default")
      (node (ref "J6") (pin "11") (pinfunction "11_11") (pintype "passive"))
    )
    (net (code "77") (name "unconnected-(J6-Pad12)") (class "Default")
      (node (ref "J6") (pin "12") (pinfunction "12_12") (pintype "passive"))
    )
  )
)
